# QuadADSR-v1.net
KiCad netlist of a schematic drawn in EAGLE
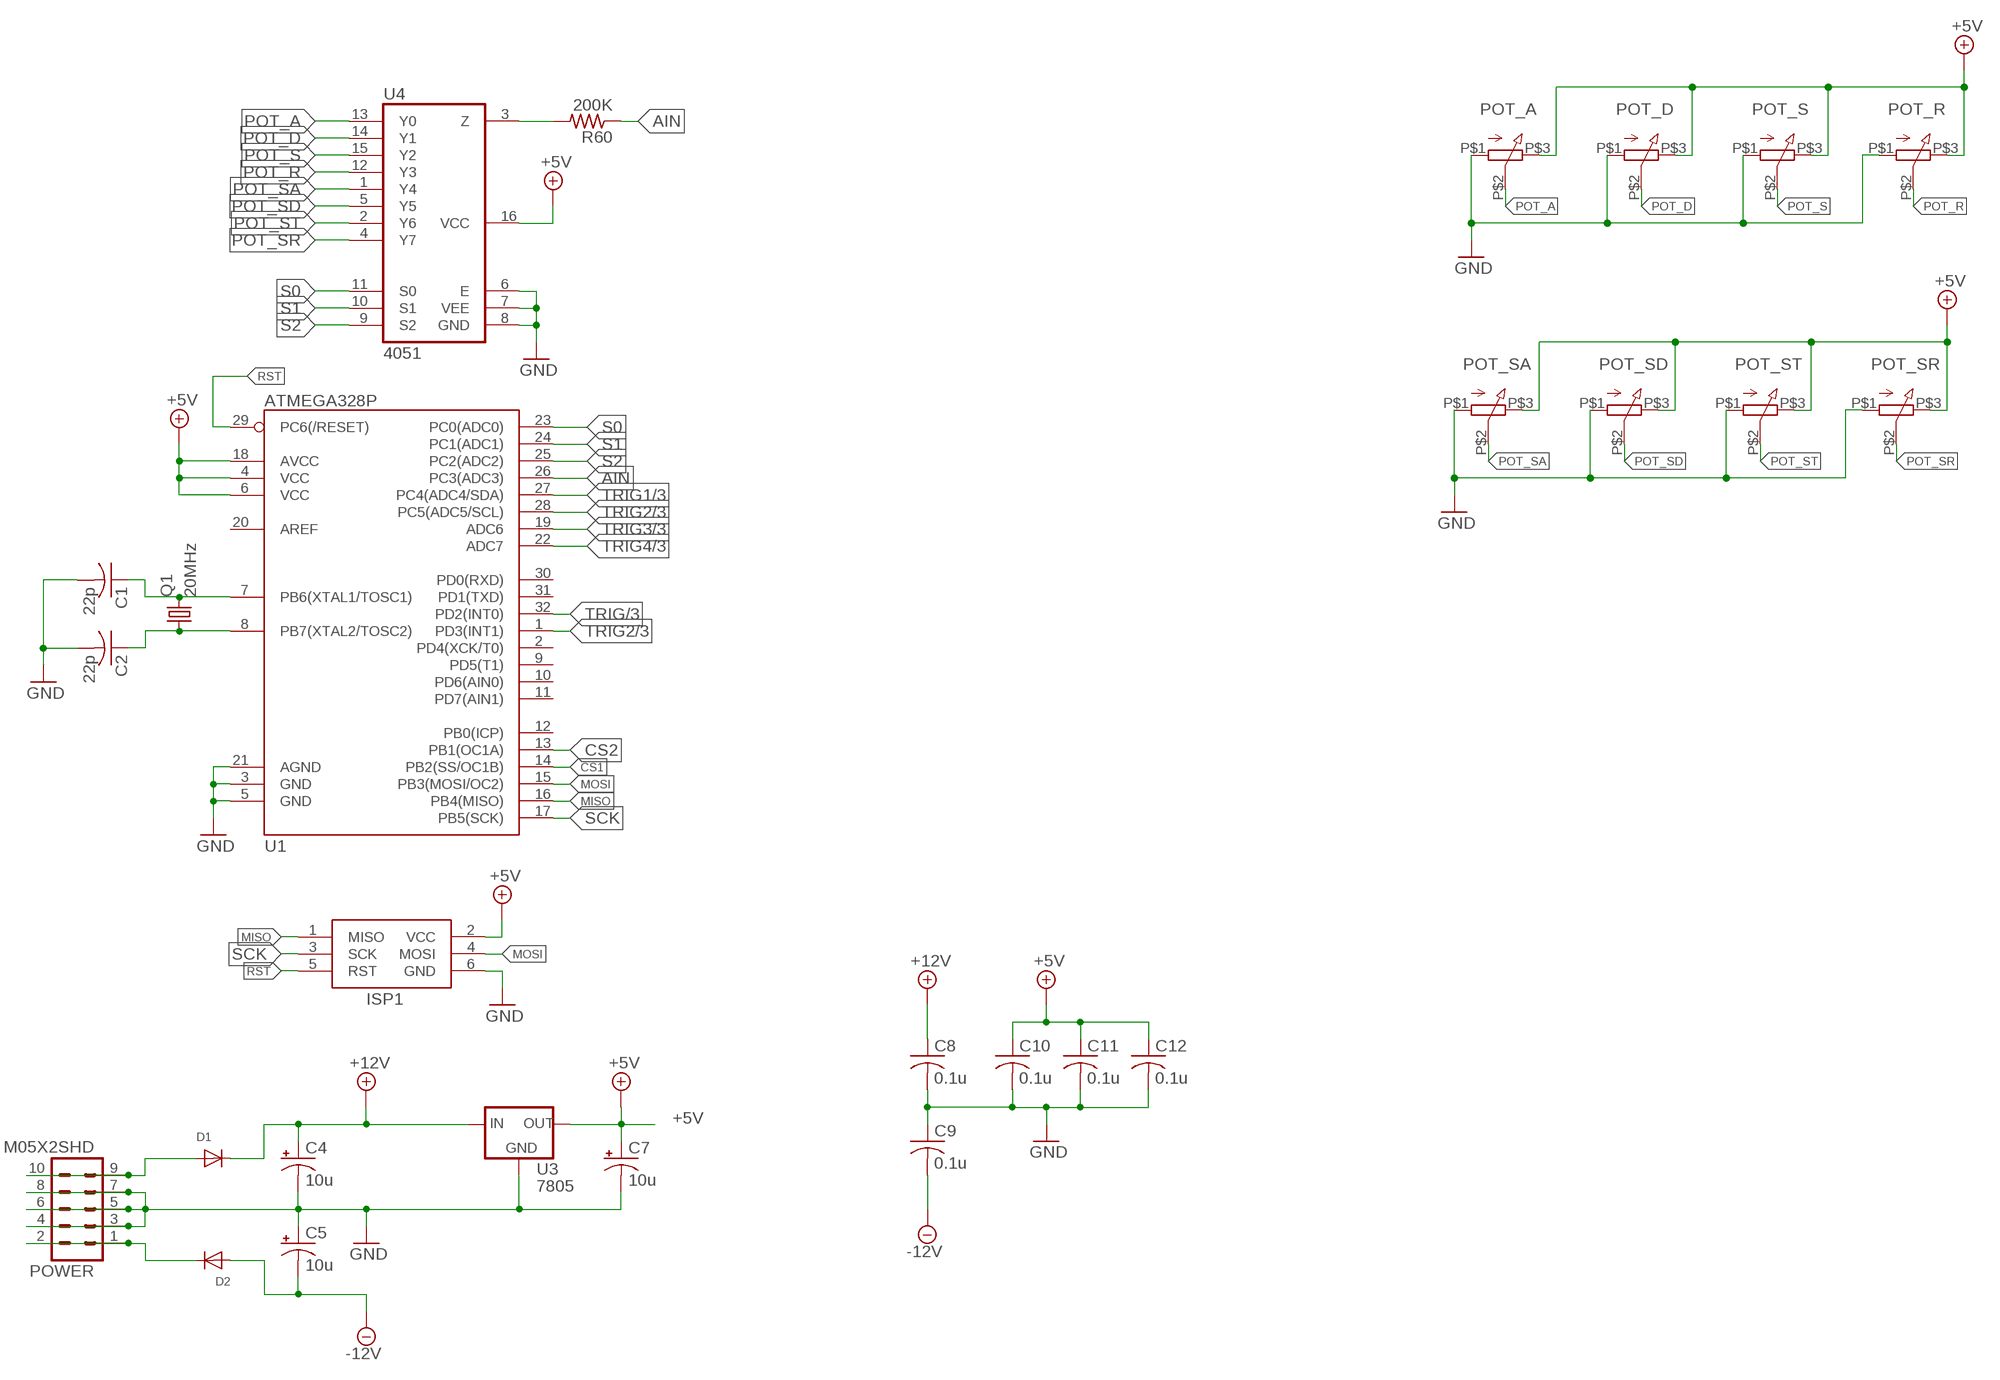
[diagram p0: schematic, sheet 1]
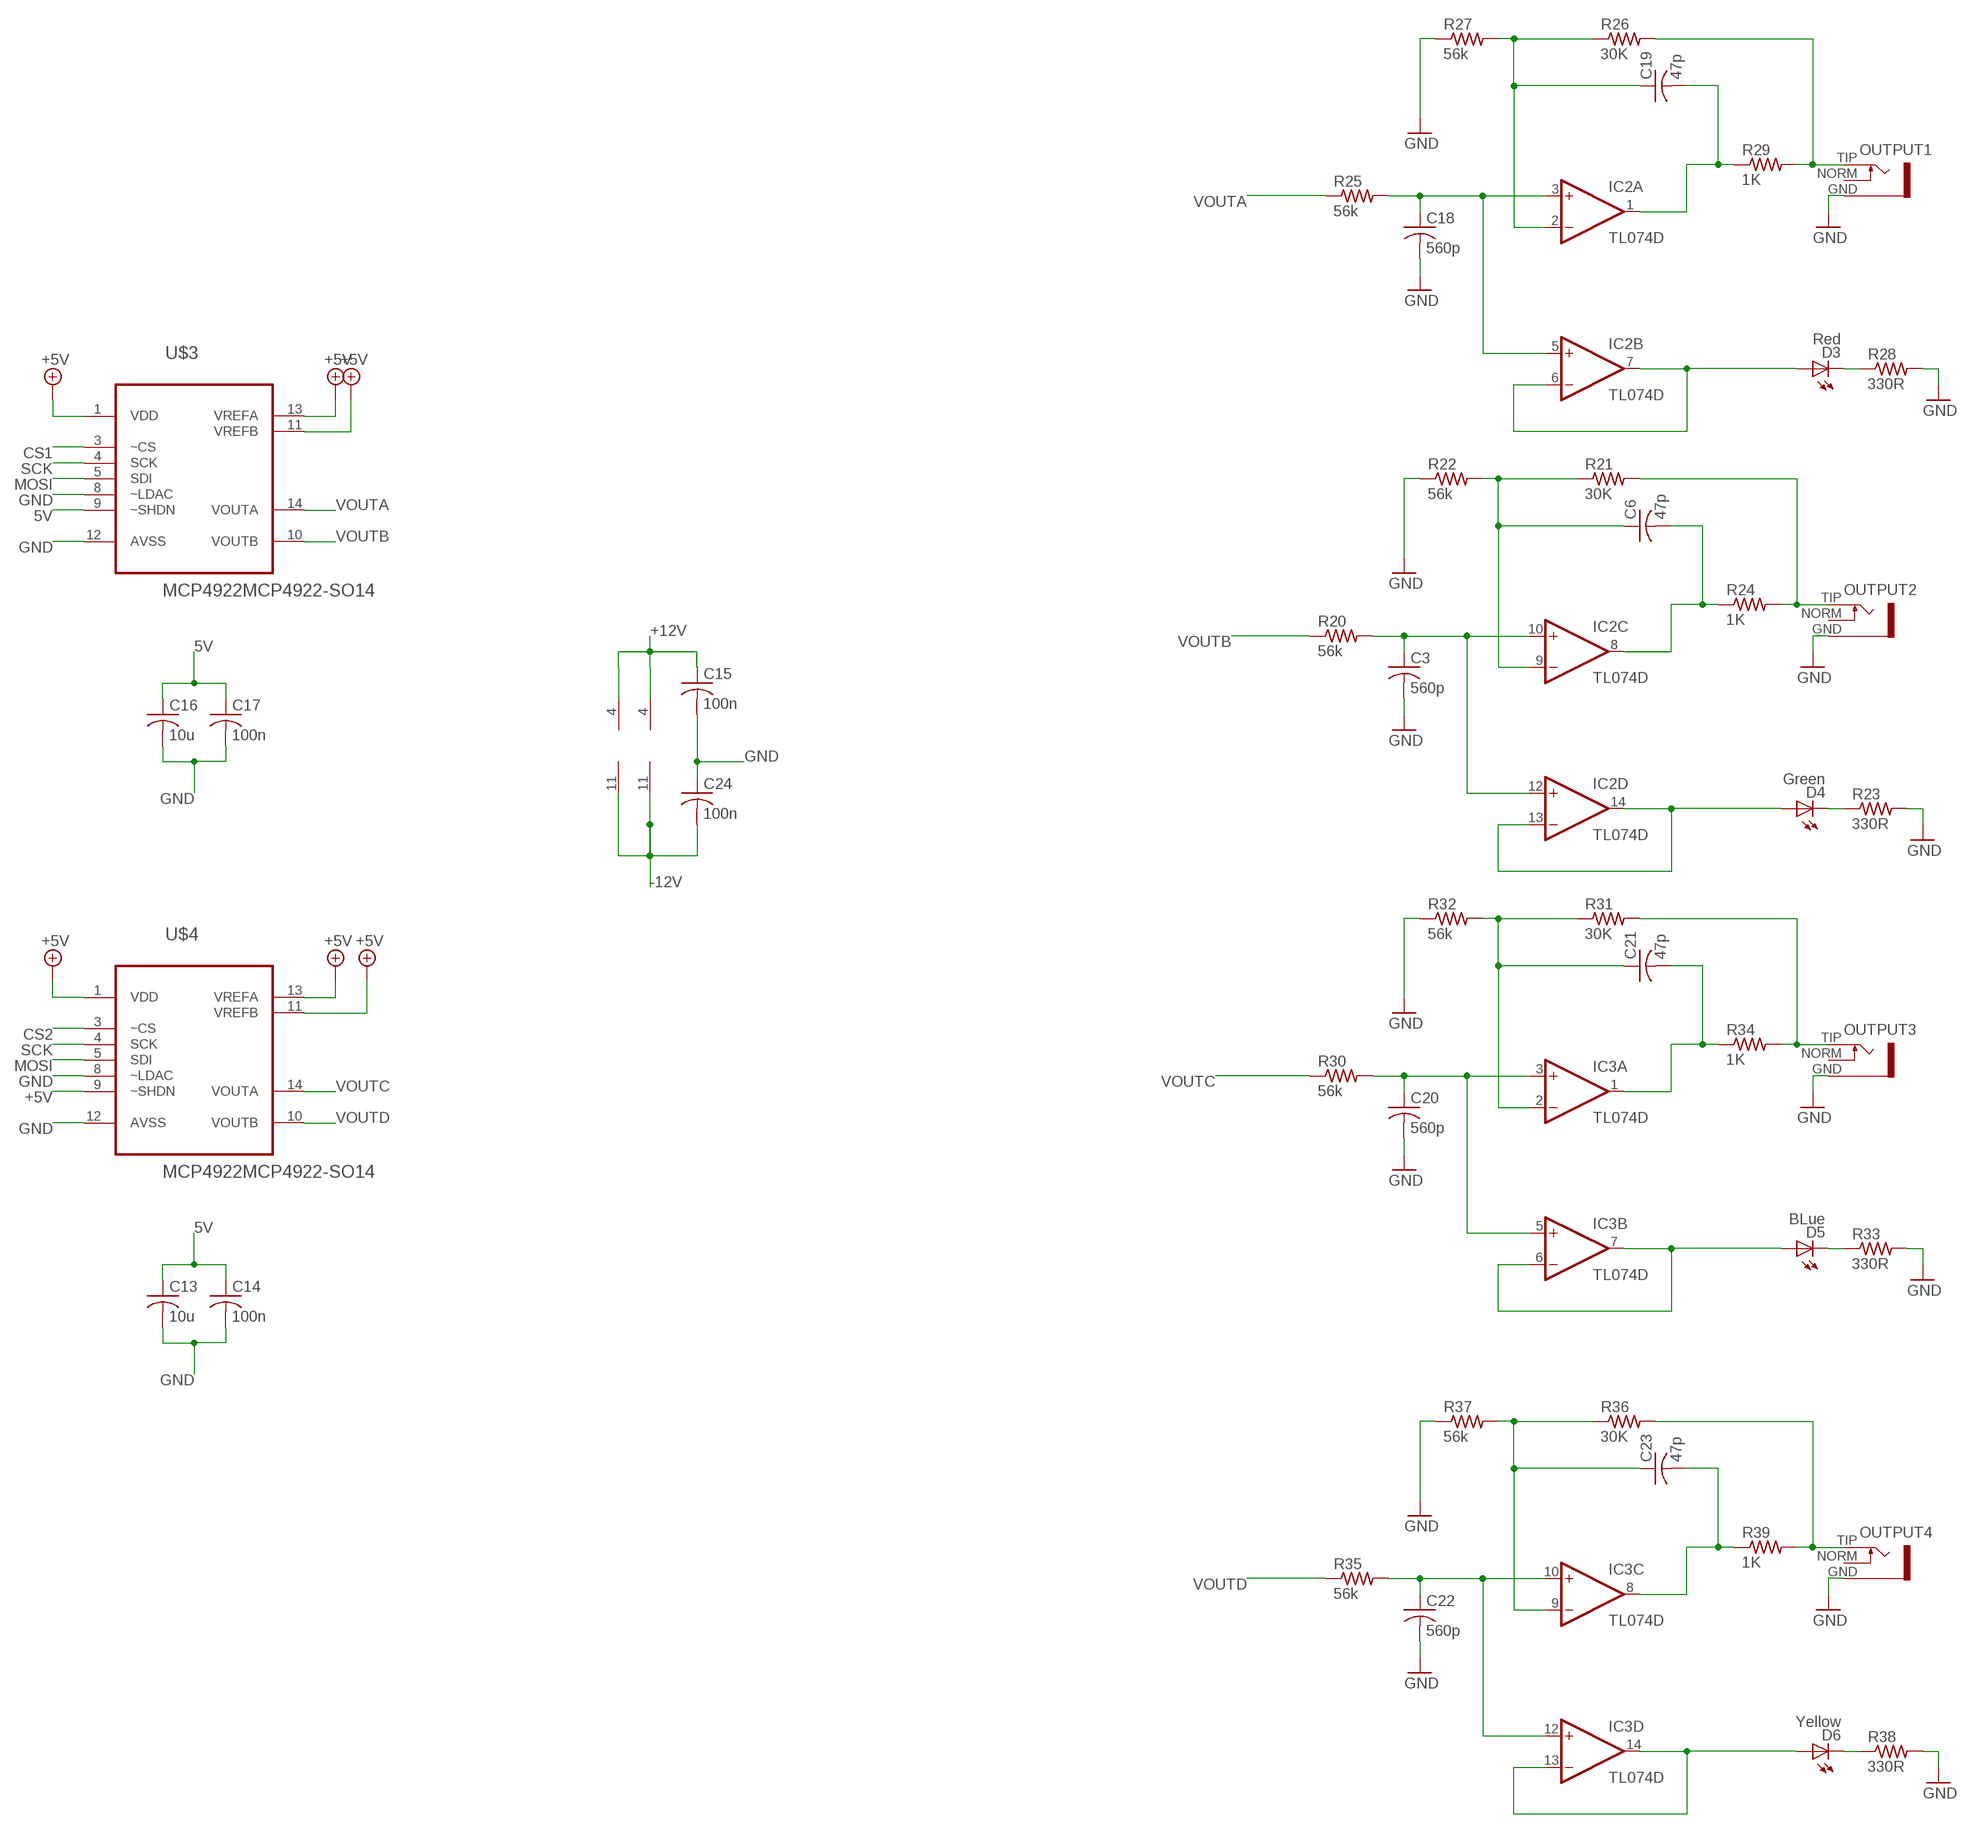
[diagram p1: schematic, sheet 2]
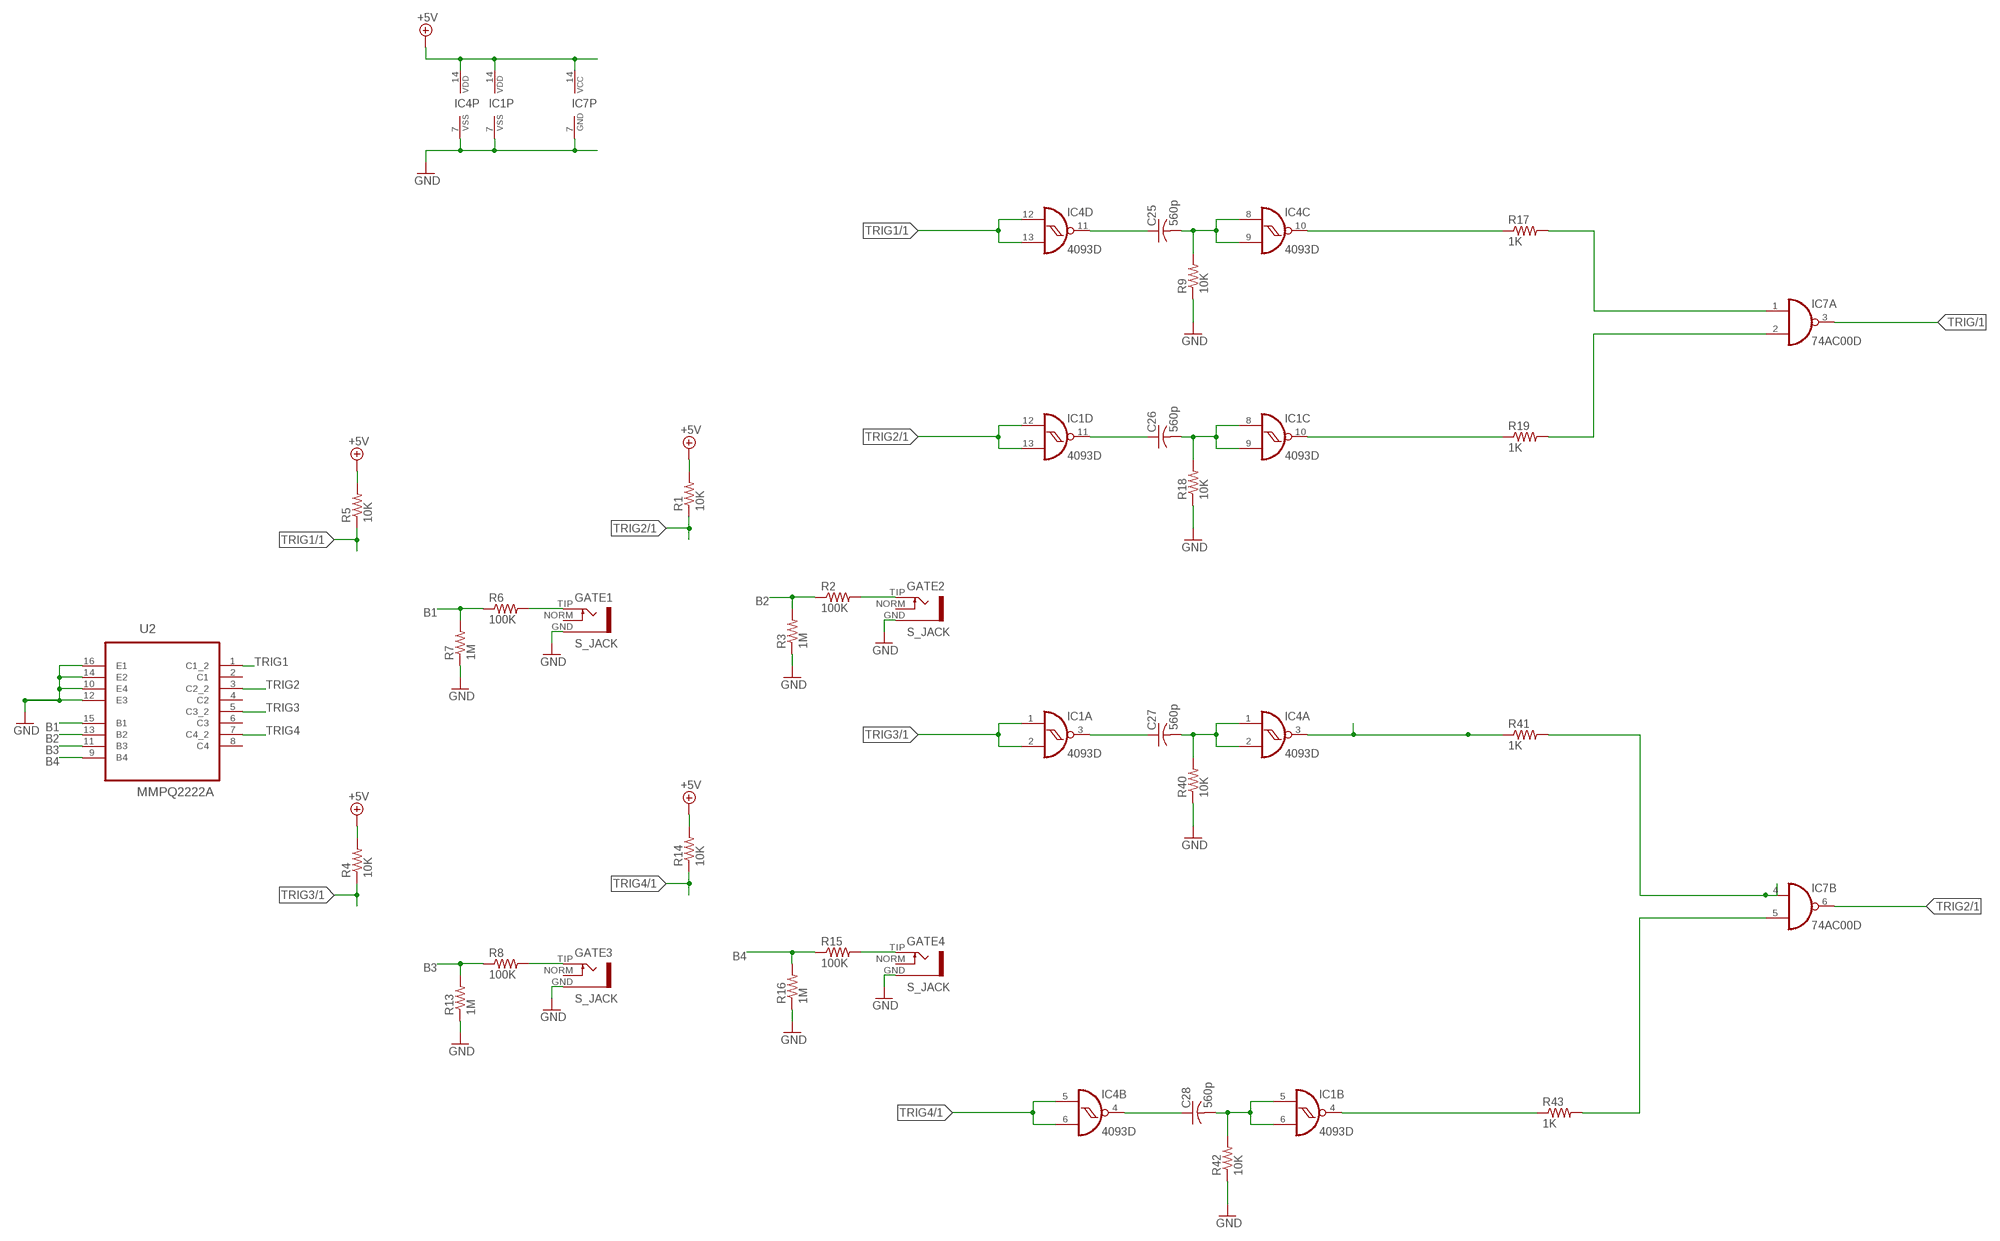
[diagram p2: schematic, sheet 3]

(export (version "E")
  (design (tool "Eeschema 10.0.6"))
  (components
    (comp (ref "C25")
      (value "560p")
      (footprint "eagle-import:C0805K")
      (libsource (lib "eagle-import") (part "C-USC0805K"))
    )
    (comp (ref "C26")
      (value "560p")
      (footprint "eagle-import:C0805K")
      (libsource (lib "eagle-import") (part "C-USC0805K"))
    )
    (comp (ref "C27")
      (value "560p")
      (footprint "eagle-import:C0805K")
      (libsource (lib "eagle-import") (part "C-USC0805K"))
    )
    (comp (ref "C28")
      (value "560p")
      (footprint "eagle-import:C0805K")
      (libsource (lib "eagle-import") (part "C-USC0805K"))
    )
    (comp (ref "GATE1")
      (value "S_JACK")
      (footprint "eagle-import:S_JACK")
      (libsource (lib "eagle-import") (part "S_JACK"))
    )
    (comp (ref "GATE2")
      (value "S_JACK")
      (footprint "eagle-import:S_JACK")
      (libsource (lib "eagle-import") (part "S_JACK"))
    )
    (comp (ref "GATE3")
      (value "S_JACK")
      (footprint "eagle-import:S_JACK")
      (libsource (lib "eagle-import") (part "S_JACK"))
    )
    (comp (ref "GATE4")
      (value "S_JACK")
      (footprint "eagle-import:S_JACK")
      (libsource (lib "eagle-import") (part "S_JACK"))
    )
    (comp (ref "IC1")
      (value "4093D")
      (footprint "eagle-import:SO14")
      (libsource (lib "eagle-import") (part "4093D"))
    )
    (comp (ref "IC4")
      (value "4093D")
      (footprint "eagle-import:SO14")
      (libsource (lib "eagle-import") (part "4093D"))
    )
    (comp (ref "IC7")
      (value "74AC00D")
      (footprint "eagle-import:SO14")
      (libsource (lib "eagle-import") (part "7400DAC"))
    )
    (comp (ref "R1")
      (value "10K")
      (footprint "eagle-import:R0805")
      (libsource (lib "eagle-import") (part "rcl_334_R-US_R0805"))
    )
    (comp (ref "R2")
      (value "100K")
      (footprint "eagle-import:R0805")
      (libsource (lib "eagle-import") (part "rcl_334_R-US_R0805"))
    )
    (comp (ref "R3")
      (value "1M")
      (footprint "eagle-import:R0805")
      (libsource (lib "eagle-import") (part "rcl_334_R-US_R0805"))
    )
    (comp (ref "R4")
      (value "10K")
      (footprint "eagle-import:R0805")
      (libsource (lib "eagle-import") (part "rcl_334_R-US_R0805"))
    )
    (comp (ref "R5")
      (value "10K")
      (footprint "eagle-import:R0805")
      (libsource (lib "eagle-import") (part "rcl_334_R-US_R0805"))
    )
    (comp (ref "R6")
      (value "100K")
      (footprint "eagle-import:R0805")
      (libsource (lib "eagle-import") (part "rcl_334_R-US_R0805"))
    )
    (comp (ref "R7")
      (value "1M")
      (footprint "eagle-import:R0805")
      (libsource (lib "eagle-import") (part "rcl_334_R-US_R0805"))
    )
    (comp (ref "R8")
      (value "100K")
      (footprint "eagle-import:R0805")
      (libsource (lib "eagle-import") (part "rcl_334_R-US_R0805"))
    )
    (comp (ref "R9")
      (value "10K")
      (footprint "eagle-import:R0805")
      (libsource (lib "eagle-import") (part "R-US_R0805"))
    )
    (comp (ref "R13")
      (value "1M")
      (footprint "eagle-import:R0805")
      (libsource (lib "eagle-import") (part "rcl_334_R-US_R0805"))
    )
    (comp (ref "R14")
      (value "10K")
      (footprint "eagle-import:R0805")
      (libsource (lib "eagle-import") (part "rcl_334_R-US_R0805"))
    )
    (comp (ref "R15")
      (value "100K")
      (footprint "eagle-import:R0805")
      (libsource (lib "eagle-import") (part "rcl_334_R-US_R0805"))
    )
    (comp (ref "R16")
      (value "1M")
      (footprint "eagle-import:R0805")
      (libsource (lib "eagle-import") (part "rcl_334_R-US_R0805"))
    )
    (comp (ref "R17")
      (value "1K")
      (footprint "eagle-import:R0805")
      (libsource (lib "eagle-import") (part "R-US_R0805"))
    )
    (comp (ref "R18")
      (value "10K")
      (footprint "eagle-import:R0805")
      (libsource (lib "eagle-import") (part "R-US_R0805"))
    )
    (comp (ref "R19")
      (value "1K")
      (footprint "eagle-import:R0805")
      (libsource (lib "eagle-import") (part "R-US_R0805"))
    )
    (comp (ref "R40")
      (value "10K")
      (footprint "eagle-import:R0805")
      (libsource (lib "eagle-import") (part "R-US_R0805"))
    )
    (comp (ref "R41")
      (value "1K")
      (footprint "eagle-import:R0805")
      (libsource (lib "eagle-import") (part "R-US_R0805"))
    )
    (comp (ref "R42")
      (value "10K")
      (footprint "eagle-import:R0805")
      (libsource (lib "eagle-import") (part "R-US_R0805"))
    )
    (comp (ref "R43")
      (value "1K")
      (footprint "eagle-import:R0805")
      (libsource (lib "eagle-import") (part "R-US_R0805"))
    )
    (comp (ref "U2")
      (value "MMPQ2222A")
      (footprint "eagle-import:SOIC127P600X175-16N")
      (libsource (lib "eagle-import") (part "MMPQ2222A"))
    )
    (comp (ref "C1")
      (value "22p")
      (footprint "eagle-import:C0805K")
      (libsource (lib "eagle-import") (part "rcl_334_C-USC0805K"))
    )
    (comp (ref "C2")
      (value "22p")
      (footprint "eagle-import:C0805K")
      (libsource (lib "eagle-import") (part "rcl_334_C-USC0805K"))
    )
    (comp (ref "C4")
      (value "10u")
      (footprint "eagle-import:153CLV-0505")
      (libsource (lib "eagle-import") (part "CPOL-US153CLV-0505"))
    )
    (comp (ref "C5")
      (value "10u")
      (footprint "eagle-import:153CLV-0505")
      (libsource (lib "eagle-import") (part "CPOL-US153CLV-0505"))
    )
    (comp (ref "C7")
      (value "10u")
      (footprint "eagle-import:153CLV-0505")
      (libsource (lib "eagle-import") (part "CPOL-US153CLV-0505"))
    )
    (comp (ref "C8")
      (value "0.1u")
      (footprint "eagle-import:C0805K")
      (libsource (lib "eagle-import") (part "rcl_334_C-USC0805K"))
    )
    (comp (ref "C9")
      (value "0.1u")
      (footprint "eagle-import:C0805K")
      (libsource (lib "eagle-import") (part "rcl_334_C-USC0805K"))
    )
    (comp (ref "C10")
      (value "0.1u")
      (footprint "eagle-import:C0805K")
      (libsource (lib "eagle-import") (part "rcl_334_C-USC0805K"))
    )
    (comp (ref "C11")
      (value "0.1u")
      (footprint "eagle-import:C0805K")
      (libsource (lib "eagle-import") (part "rcl_334_C-USC0805K"))
    )
    (comp (ref "C12")
      (value "0.1u")
      (footprint "eagle-import:C0805K")
      (libsource (lib "eagle-import") (part "rcl_334_C-USC0805K"))
    )
    (comp (ref "D1")
      (value "DIODESMA")
      (footprint "eagle-import:SMADIODE")
      (libsource (lib "eagle-import") (part "DIODESMA"))
    )
    (comp (ref "D2")
      (value "DIODESMA")
      (footprint "eagle-import:SMADIODE")
      (libsource (lib "eagle-import") (part "DIODESMA"))
    )
    (comp (ref "ISP1")
      (value "AVRISP-6")
      (footprint "eagle-import:AVRISP")
      (libsource (lib "eagle-import") (part "AVRISP-6"))
    )
    (comp (ref "POT_A")
      (value "Q-POT")
      (footprint "eagle-import:Q-POT")
      (libsource (lib "eagle-import") (part "Q-POT"))
    )
    (comp (ref "POT_D")
      (value "Q-POT")
      (footprint "eagle-import:Q-POT")
      (libsource (lib "eagle-import") (part "Q-POT"))
    )
    (comp (ref "POT_R")
      (value "Q-POT")
      (footprint "eagle-import:Q-POT")
      (libsource (lib "eagle-import") (part "Q-POT"))
    )
    (comp (ref "POT_S")
      (value "Q-POT")
      (footprint "eagle-import:Q-POT")
      (libsource (lib "eagle-import") (part "Q-POT"))
    )
    (comp (ref "POT_SA")
      (value "Q-POT")
      (footprint "eagle-import:Q-POT")
      (libsource (lib "eagle-import") (part "Q-POT"))
    )
    (comp (ref "POT_SD")
      (value "Q-POT")
      (footprint "eagle-import:Q-POT")
      (libsource (lib "eagle-import") (part "Q-POT"))
    )
    (comp (ref "POT_SR")
      (value "Q-POT")
      (footprint "eagle-import:Q-POT")
      (libsource (lib "eagle-import") (part "Q-POT"))
    )
    (comp (ref "POT_ST")
      (value "Q-POT")
      (footprint "eagle-import:Q-POT")
      (libsource (lib "eagle-import") (part "Q-POT"))
    )
    (comp (ref "POWER")
      (value "M05X2SHD")
      (footprint "eagle-import:2X5-SHROUDED")
      (libsource (lib "eagle-import") (part "M05X2SHD"))
    )
    (comp (ref "Q1")
      (value "20MHz")
      (footprint "eagle-import:HC49UP")
      (libsource (lib "eagle-import") (part "CRYSTALHC49UP"))
    )
    (comp (ref "R60")
      (value "200K")
      (footprint "eagle-import:R0805")
      (libsource (lib "eagle-import") (part "R-US_R0805"))
    )
    (comp (ref "U1")
      (value "ATMEGA328P")
      (footprint "eagle-import:TQFP32-08")
      (libsource (lib "eagle-import") (part "ATMEGA328_SMT"))
    )
    (comp (ref "U3")
      (value "7805")
      (footprint "eagle-import:V-REG")
      (libsource (lib "eagle-import") (part "V-REG"))
    )
    (comp (ref "U4")
      (value "4051")
      (footprint "eagle-import:N2222_ARRAY")
      (libsource (lib "eagle-import") (part "MUX!"))
    )
    (comp (ref "C3")
      (value "560p")
      (footprint "eagle-import:C0805K")
      (libsource (lib "eagle-import") (part "C-USC0805K"))
    )
    (comp (ref "C6")
      (value "47p")
      (footprint "eagle-import:C0805K")
      (libsource (lib "eagle-import") (part "C-USC0805K"))
    )
    (comp (ref "C13")
      (value "10u")
      (footprint "eagle-import:C0805K")
      (libsource (lib "eagle-import") (part "rcl_334_C-USC0805K"))
    )
    (comp (ref "C14")
      (value "100n")
      (footprint "eagle-import:C0805K")
      (libsource (lib "eagle-import") (part "rcl_334_C-USC0805K"))
    )
    (comp (ref "C15")
      (value "100n")
      (footprint "eagle-import:C0805K")
      (libsource (lib "eagle-import") (part "rcl_334_C-USC0805K"))
    )
    (comp (ref "C16")
      (value "10u")
      (footprint "eagle-import:C0805K")
      (libsource (lib "eagle-import") (part "rcl_334_C-USC0805K"))
    )
    (comp (ref "C17")
      (value "100n")
      (footprint "eagle-import:C0805K")
      (libsource (lib "eagle-import") (part "rcl_334_C-USC0805K"))
    )
    (comp (ref "C18")
      (value "560p")
      (footprint "eagle-import:C0805K")
      (libsource (lib "eagle-import") (part "C-USC0805K"))
    )
    (comp (ref "C19")
      (value "47p")
      (footprint "eagle-import:C0805K")
      (libsource (lib "eagle-import") (part "C-USC0805K"))
    )
    (comp (ref "C20")
      (value "560p")
      (footprint "eagle-import:C0805K")
      (libsource (lib "eagle-import") (part "C-USC0805K"))
    )
    (comp (ref "C21")
      (value "47p")
      (footprint "eagle-import:C0805K")
      (libsource (lib "eagle-import") (part "C-USC0805K"))
    )
    (comp (ref "C22")
      (value "560p")
      (footprint "eagle-import:C0805K")
      (libsource (lib "eagle-import") (part "C-USC0805K"))
    )
    (comp (ref "C23")
      (value "47p")
      (footprint "eagle-import:C0805K")
      (libsource (lib "eagle-import") (part "C-USC0805K"))
    )
    (comp (ref "C24")
      (value "100n")
      (footprint "eagle-import:C0805K")
      (libsource (lib "eagle-import") (part "rcl_334_C-USC0805K"))
    )
    (comp (ref "D3")
      (value "Red")
      (footprint "eagle-import:LED5MM")
      (libsource (lib "eagle-import") (part "LED5MM"))
    )
    (comp (ref "D4")
      (value "Green")
      (footprint "eagle-import:LED5MM")
      (libsource (lib "eagle-import") (part "LED5MM"))
    )
    (comp (ref "D5")
      (value "BLue")
      (footprint "eagle-import:LED5MM")
      (libsource (lib "eagle-import") (part "LED5MM"))
    )
    (comp (ref "D6")
      (value "Yellow")
      (footprint "eagle-import:LED5MM")
      (libsource (lib "eagle-import") (part "LED5MM"))
    )
    (comp (ref "IC2")
      (value "TL074D")
      (footprint "eagle-import:SO14")
      (libsource (lib "eagle-import") (part "TL074D"))
    )
    (comp (ref "IC3")
      (value "TL074D")
      (footprint "eagle-import:SO14")
      (libsource (lib "eagle-import") (part "TL074D"))
    )
    (comp (ref "OUTPUT1")
      (value "S_JACK")
      (footprint "eagle-import:S_JACK")
      (libsource (lib "eagle-import") (part "S_JACK"))
    )
    (comp (ref "OUTPUT2")
      (value "S_JACK")
      (footprint "eagle-import:S_JACK")
      (libsource (lib "eagle-import") (part "S_JACK"))
    )
    (comp (ref "OUTPUT3")
      (value "S_JACK")
      (footprint "eagle-import:S_JACK")
      (libsource (lib "eagle-import") (part "S_JACK"))
    )
    (comp (ref "OUTPUT4")
      (value "S_JACK")
      (footprint "eagle-import:S_JACK")
      (libsource (lib "eagle-import") (part "S_JACK"))
    )
    (comp (ref "R20")
      (value "56k")
      (footprint "eagle-import:R0805")
      (libsource (lib "eagle-import") (part "R-US_R0805"))
    )
    (comp (ref "R21")
      (value "30K")
      (footprint "eagle-import:R0805")
      (libsource (lib "eagle-import") (part "R-US_R0805"))
    )
    (comp (ref "R22")
      (value "56k")
      (footprint "eagle-import:R0805")
      (libsource (lib "eagle-import") (part "R-US_R0805"))
    )
    (comp (ref "R23")
      (value "330R")
      (footprint "eagle-import:R0805")
      (libsource (lib "eagle-import") (part "R-US_R0805"))
    )
    (comp (ref "R24")
      (value "1K")
      (footprint "eagle-import:R0805")
      (libsource (lib "eagle-import") (part "R-US_R0805"))
    )
    (comp (ref "R25")
      (value "56k")
      (footprint "eagle-import:R0805")
      (libsource (lib "eagle-import") (part "R-US_R0805"))
    )
    (comp (ref "R26")
      (value "30K")
      (footprint "eagle-import:R0805")
      (libsource (lib "eagle-import") (part "R-US_R0805"))
    )
    (comp (ref "R27")
      (value "56k")
      (footprint "eagle-import:R0805")
      (libsource (lib "eagle-import") (part "R-US_R0805"))
    )
    (comp (ref "R28")
      (value "330R")
      (footprint "eagle-import:R0805")
      (libsource (lib "eagle-import") (part "R-US_R0805"))
    )
    (comp (ref "R29")
      (value "1K")
      (footprint "eagle-import:R0805")
      (libsource (lib "eagle-import") (part "R-US_R0805"))
    )
    (comp (ref "R30")
      (value "56k")
      (footprint "eagle-import:R0805")
      (libsource (lib "eagle-import") (part "R-US_R0805"))
    )
    (comp (ref "R31")
      (value "30K")
      (footprint "eagle-import:R0805")
      (libsource (lib "eagle-import") (part "R-US_R0805"))
    )
    (comp (ref "R32")
      (value "56k")
      (footprint "eagle-import:R0805")
      (libsource (lib "eagle-import") (part "R-US_R0805"))
    )
    (comp (ref "R33")
      (value "330R")
      (footprint "eagle-import:R0805")
      (libsource (lib "eagle-import") (part "R-US_R0805"))
    )
    (comp (ref "R34")
      (value "1K")
      (footprint "eagle-import:R0805")
      (libsource (lib "eagle-import") (part "R-US_R0805"))
    )
    (comp (ref "R35")
      (value "56k")
      (footprint "eagle-import:R0805")
      (libsource (lib "eagle-import") (part "R-US_R0805"))
    )
    (comp (ref "R36")
      (value "30K")
      (footprint "eagle-import:R0805")
      (libsource (lib "eagle-import") (part "R-US_R0805"))
    )
    (comp (ref "R37")
      (value "56k")
      (footprint "eagle-import:R0805")
      (libsource (lib "eagle-import") (part "R-US_R0805"))
    )
    (comp (ref "R38")
      (value "330R")
      (footprint "eagle-import:R0805")
      (libsource (lib "eagle-import") (part "R-US_R0805"))
    )
    (comp (ref "R39")
      (value "1K")
      (footprint "eagle-import:R0805")
      (libsource (lib "eagle-import") (part "R-US_R0805"))
    )
    (comp (ref "U$3")
      (value "MCP4922MCP4922-SO14")
      (footprint "eagle-import:SO14")
      (libsource (lib "eagle-import") (part "MCP4922MCP4922-SO14"))
    )
    (comp (ref "U$4")
      (value "MCP4922MCP4922-SO14")
      (footprint "eagle-import:SO14")
      (libsource (lib "eagle-import") (part "MCP4922MCP4922-SO14"))
    )
  )
  (nets
    (net (code "1") (name "+5V") (class "Default")
      (node (ref "C10") (pin "1") (pinfunction "1_1") (pintype "passive"))
      (node (ref "C11") (pin "1") (pinfunction "1_1") (pintype "passive"))
      (node (ref "C12") (pin "1") (pinfunction "1_1") (pintype "passive"))
      (node (ref "C7") (pin "+") (pinfunction "+_+") (pintype "passive"))
      (node (ref "IC1") (pin "14") (pinfunction "VDD_14") (pintype "power_in"))
      (node (ref "IC4") (pin "14") (pinfunction "VDD_14") (pintype "power_in"))
      (node (ref "IC7") (pin "14") (pinfunction "VCC_14") (pintype "power_in"))
      (node (ref "ISP1") (pin "2") (pinfunction "VCC_2") (pintype "power_in"))
      (node (ref "POT_A") (pin "P$3") (pinfunction "3_P$3") (pintype "passive"))
      (node (ref "POT_D") (pin "P$3") (pinfunction "3_P$3") (pintype "passive"))
      (node (ref "POT_R") (pin "P$3") (pinfunction "3_P$3") (pintype "passive"))
      (node (ref "POT_S") (pin "P$3") (pinfunction "3_P$3") (pintype "passive"))
      (node (ref "POT_SA") (pin "P$3") (pinfunction "3_P$3") (pintype "passive"))
      (node (ref "POT_SD") (pin "P$3") (pinfunction "3_P$3") (pintype "passive"))
      (node (ref "POT_SR") (pin "P$3") (pinfunction "3_P$3") (pintype "passive"))
      (node (ref "POT_ST") (pin "P$3") (pinfunction "3_P$3") (pintype "passive"))
      (node (ref "R1") (pin "2") (pinfunction "2_2") (pintype "passive"))
      (node (ref "R14") (pin "2") (pinfunction "2_2") (pintype "passive"))
      (node (ref "R4") (pin "2") (pinfunction "2_2") (pintype "passive"))
      (node (ref "R5") (pin "2") (pinfunction "2_2") (pintype "passive"))
      (node (ref "U$3") (pin "1") (pinfunction "VDD_1") (pintype "power_in"))
      (node (ref "U$3") (pin "11") (pinfunction "VREFB_11") (pintype "bidirectional"))
      (node (ref "U$3") (pin "13") (pinfunction "VREFA_13") (pintype "input"))
      (node (ref "U$4") (pin "1") (pinfunction "VDD_1") (pintype "power_in"))
      (node (ref "U$4") (pin "11") (pinfunction "VREFB_11") (pintype "bidirectional"))
      (node (ref "U$4") (pin "13") (pinfunction "VREFA_13") (pintype "input"))
      (node (ref "U$4") (pin "9") (pinfunction "~{SHDN}_9") (pintype "bidirectional"))
      (node (ref "U1") (pin "18") (pinfunction "AVCC_18") (pintype "bidirectional"))
      (node (ref "U1") (pin "4") (pinfunction "VCC_4") (pintype "bidirectional"))
      (node (ref "U1") (pin "6") (pinfunction "VCC_6") (pintype "bidirectional"))
      (node (ref "U3") (pin "3") (pinfunction "OUT_3") (pintype "passive"))
      (node (ref "U4") (pin "16") (pinfunction "VCC_16") (pintype "input"))
    )
    (net (code "2") (name "+12V") (class "Default")
      (node (ref "C15") (pin "1") (pinfunction "1_1") (pintype "passive"))
      (node (ref "C4") (pin "+") (pinfunction "+_+") (pintype "passive"))
      (node (ref "C8") (pin "1") (pinfunction "1_1") (pintype "passive"))
      (node (ref "D1") (pin "C") (pinfunction "C_C") (pintype "passive"))
      (node (ref "IC2") (pin "4") (pinfunction "V+_4") (pintype "power_in"))
      (node (ref "IC3") (pin "4") (pinfunction "V+_4") (pintype "power_in"))
      (node (ref "U3") (pin "1") (pinfunction "IN_1") (pintype "input"))
    )
    (net (code "3") (name "-12V") (class "Default")
      (node (ref "C24") (pin "2") (pinfunction "2_2") (pintype "passive"))
      (node (ref "C5") (pin "-") (pinfunction "-_-") (pintype "passive"))
      (node (ref "C9") (pin "2") (pinfunction "2_2") (pintype "passive"))
      (node (ref "D2") (pin "A") (pinfunction "A_A") (pintype "passive"))
      (node (ref "IC2") (pin "11") (pinfunction "V-_11") (pintype "power_in"))
      (node (ref "IC3") (pin "11") (pinfunction "V-_11") (pintype "power_in"))
    )
    (net (code "4") (name "5V") (class "Default")
      (node (ref "C13") (pin "1") (pinfunction "1_1") (pintype "passive"))
      (node (ref "C14") (pin "1") (pinfunction "1_1") (pintype "passive"))
      (node (ref "C16") (pin "1") (pinfunction "1_1") (pintype "passive"))
      (node (ref "C17") (pin "1") (pinfunction "1_1") (pintype "passive"))
      (node (ref "U$3") (pin "9") (pinfunction "~{SHDN}_9") (pintype "bidirectional"))
    )
    (net (code "5") (name "AIN") (class "Default")
      (node (ref "R60") (pin "1") (pinfunction "1_1") (pintype "passive"))
      (node (ref "U1") (pin "26") (pinfunction "PC3(ADC3)_26") (pintype "bidirectional"))
    )
    (net (code "6") (name "B1") (class "Default")
      (node (ref "R6") (pin "1") (pinfunction "1_1") (pintype "passive"))
      (node (ref "R7") (pin "2") (pinfunction "2_2") (pintype "passive"))
      (node (ref "U2") (pin "15") (pinfunction "B1_15") (pintype "passive"))
    )
    (net (code "7") (name "B2") (class "Default")
      (node (ref "R2") (pin "1") (pinfunction "1_1") (pintype "passive"))
      (node (ref "R3") (pin "2") (pinfunction "2_2") (pintype "passive"))
      (node (ref "U2") (pin "13") (pinfunction "B2_13") (pintype "passive"))
    )
    (net (code "8") (name "B3") (class "Default")
      (node (ref "R13") (pin "2") (pinfunction "2_2") (pintype "passive"))
      (node (ref "R8") (pin "1") (pinfunction "1_1") (pintype "passive"))
      (node (ref "U2") (pin "11") (pinfunction "B3_11") (pintype "passive"))
    )
    (net (code "9") (name "B4") (class "Default")
      (node (ref "R15") (pin "1") (pinfunction "1_1") (pintype "passive"))
      (node (ref "R16") (pin "2") (pinfunction "2_2") (pintype "passive"))
      (node (ref "U2") (pin "9") (pinfunction "B4_9") (pintype "passive"))
    )
    (net (code "10") (name "CS1") (class "Default")
      (node (ref "U$3") (pin "3") (pinfunction "~{CS}_3") (pintype "input"))
      (node (ref "U1") (pin "14") (pinfunction "PB2(SS/OC1B)_14") (pintype "bidirectional"))
    )
    (net (code "11") (name "CS2") (class "Default")
      (node (ref "U$4") (pin "3") (pinfunction "~{CS}_3") (pintype "input"))
      (node (ref "U1") (pin "13") (pinfunction "PB1(OC1A)_13") (pintype "bidirectional"))
    )
    (net (code "12") (name "GND") (class "Default")
      (node (ref "C1") (pin "2") (pinfunction "2_2") (pintype "passive"))
      (node (ref "C10") (pin "2") (pinfunction "2_2") (pintype "passive"))
      (node (ref "C11") (pin "2") (pinfunction "2_2") (pintype "passive"))
      (node (ref "C12") (pin "2") (pinfunction "2_2") (pintype "passive"))
      (node (ref "C13") (pin "2") (pinfunction "2_2") (pintype "passive"))
      (node (ref "C14") (pin "2") (pinfunction "2_2") (pintype "passive"))
      (node (ref "C15") (pin "2") (pinfunction "2_2") (pintype "passive"))
      (node (ref "C16") (pin "2") (pinfunction "2_2") (pintype "passive"))
      (node (ref "C17") (pin "2") (pinfunction "2_2") (pintype "passive"))
      (node (ref "C18") (pin "2") (pinfunction "2_2") (pintype "passive"))
      (node (ref "C2") (pin "2") (pinfunction "2_2") (pintype "passive"))
      (node (ref "C20") (pin "2") (pinfunction "2_2") (pintype "passive"))
      (node (ref "C22") (pin "2") (pinfunction "2_2") (pintype "passive"))
      (node (ref "C24") (pin "1") (pinfunction "1_1") (pintype "passive"))
      (node (ref "C3") (pin "2") (pinfunction "2_2") (pintype "passive"))
      (node (ref "C4") (pin "-") (pinfunction "-_-") (pintype "passive"))
      (node (ref "C5") (pin "+") (pinfunction "+_+") (pintype "passive"))
      (node (ref "C7") (pin "-") (pinfunction "-_-") (pintype "passive"))
      (node (ref "C8") (pin "2") (pinfunction "2_2") (pintype "passive"))
      (node (ref "C9") (pin "1") (pinfunction "1_1") (pintype "passive"))
      (node (ref "GATE1") (pin "GND") (pinfunction "GND_GND") (pintype "passive"))
      (node (ref "GATE2") (pin "GND") (pinfunction "GND_GND") (pintype "passive"))
      (node (ref "GATE3") (pin "GND") (pinfunction "GND_GND") (pintype "passive"))
      (node (ref "GATE4") (pin "GND") (pinfunction "GND_GND") (pintype "passive"))
      (node (ref "IC1") (pin "7") (pinfunction "VSS_7") (pintype "power_in"))
      (node (ref "IC4") (pin "7") (pinfunction "VSS_7") (pintype "power_in"))
      (node (ref "IC7") (pin "7") (pinfunction "GND_7") (pintype "power_in"))
      (node (ref "ISP1") (pin "6") (pinfunction "GND_6") (pintype "power_in"))
      (node (ref "OUTPUT1") (pin "GND") (pinfunction "GND_GND") (pintype "passive"))
      (node (ref "OUTPUT2") (pin "GND") (pinfunction "GND_GND") (pintype "passive"))
      (node (ref "OUTPUT3") (pin "GND") (pinfunction "GND_GND") (pintype "passive"))
      (node (ref "OUTPUT4") (pin "GND") (pinfunction "GND_GND") (pintype "passive"))
      (node (ref "POT_A") (pin "P$1") (pinfunction "1_P$1") (pintype "passive"))
      (node (ref "POT_D") (pin "P$1") (pinfunction "1_P$1") (pintype "passive"))
      (node (ref "POT_R") (pin "P$1") (pinfunction "1_P$1") (pintype "passive"))
      (node (ref "POT_S") (pin "P$1") (pinfunction "1_P$1") (pintype "passive"))
      (node (ref "POT_SA") (pin "P$1") (pinfunction "1_P$1") (pintype "passive"))
      (node (ref "POT_SD") (pin "P$1") (pinfunction "1_P$1") (pintype "passive"))
      (node (ref "POT_SR") (pin "P$1") (pinfunction "1_P$1") (pintype "passive"))
      (node (ref "POT_ST") (pin "P$1") (pinfunction "1_P$1") (pintype "passive"))
      (node (ref "POWER") (pin "3") (pinfunction "3_3") (pintype "passive"))
      (node (ref "POWER") (pin "4") (pinfunction "4_4") (pintype "passive"))
      (node (ref "POWER") (pin "5") (pinfunction "5_5") (pintype "passive"))
      (node (ref "POWER") (pin "6") (pinfunction "6_6") (pintype "passive"))
      (node (ref "POWER") (pin "7") (pinfunction "7_7") (pintype "passive"))
      (node (ref "POWER") (pin "8") (pinfunction "8_8") (pintype "passive"))
      (node (ref "R13") (pin "1") (pinfunction "1_1") (pintype "passive"))
      (node (ref "R16") (pin "1") (pinfunction "1_1") (pintype "passive"))
      (node (ref "R18") (pin "1") (pinfunction "1_1") (pintype "passive"))
      (node (ref "R22") (pin "1") (pinfunction "1_1") (pintype "passive"))
      (node (ref "R23") (pin "2") (pinfunction "2_2") (pintype "passive"))
      (node (ref "R27") (pin "1") (pinfunction "1_1") (pintype "passive"))
      (node (ref "R28") (pin "2") (pinfunction "2_2") (pintype "passive"))
      (node (ref "R3") (pin "1") (pinfunction "1_1") (pintype "passive"))
      (node (ref "R32") (pin "1") (pinfunction "1_1") (pintype "passive"))
      (node (ref "R33") (pin "2") (pinfunction "2_2") (pintype "passive"))
      (node (ref "R37") (pin "1") (pinfunction "1_1") (pintype "passive"))
      (node (ref "R38") (pin "2") (pinfunction "2_2") (pintype "passive"))
      (node (ref "R40") (pin "1") (pinfunction "1_1") (pintype "passive"))
      (node (ref "R42") (pin "1") (pinfunction "1_1") (pintype "passive"))
      (node (ref "R7") (pin "1") (pinfunction "1_1") (pintype "passive"))
      (node (ref "R9") (pin "1") (pinfunction "1_1") (pintype "passive"))
      (node (ref "U$3") (pin "12") (pinfunction "AVSS_12") (pintype "passive"))
      (node (ref "U$3") (pin "8") (pinfunction "~{LDAC}_8") (pintype "input"))
      (node (ref "U$4") (pin "12") (pinfunction "AVSS_12") (pintype "passive"))
      (node (ref "U$4") (pin "8") (pinfunction "~{LDAC}_8") (pintype "input"))
      (node (ref "U1") (pin "21") (pinfunction "AGND_21") (pintype "bidirectional"))
      (node (ref "U1") (pin "3") (pinfunction "GND_3") (pintype "bidirectional"))
      (node (ref "U1") (pin "5") (pinfunction "GND_5") (pintype "bidirectional"))
      (node (ref "U2") (pin "10") (pinfunction "E4_10") (pintype "passive"))
      (node (ref "U2") (pin "12") (pinfunction "E3_12") (pintype "passive"))
      (node (ref "U2") (pin "14") (pinfunction "E2_14") (pintype "passive"))
      (node (ref "U2") (pin "16") (pinfunction "E1_16") (pintype "passive"))
      (node (ref "U3") (pin "4") (pinfunction "GND_4") (pintype "input"))
      (node (ref "U4") (pin "6") (pinfunction "E_6") (pintype "bidirectional"))
      (node (ref "U4") (pin "7") (pinfunction "VEE_7") (pintype "bidirectional"))
      (node (ref "U4") (pin "8") (pinfunction "GND_8") (pintype "bidirectional"))
    )
    (net (code "13") (name "MISO") (class "Default")
      (node (ref "ISP1") (pin "1") (pinfunction "MISO_1") (pintype "input"))
      (node (ref "U1") (pin "16") (pinfunction "PB4(MISO)_16") (pintype "bidirectional"))
    )
    (net (code "14") (name "MOSI") (class "Default")
      (node (ref "ISP1") (pin "4") (pinfunction "MOSI_4") (pintype "output"))
      (node (ref "U$3") (pin "5") (pinfunction "SDI_5") (pintype "input"))
      (node (ref "U$4") (pin "5") (pinfunction "SDI_5") (pintype "input"))
      (node (ref "U1") (pin "15") (pinfunction "PB3(MOSI/OC2)_15") (pintype "bidirectional"))
    )
    (net (code "15") (name "Net-(D1-PadA)") (class "Default")
      (node (ref "D1") (pin "A") (pinfunction "A_A") (pintype "passive"))
      (node (ref "POWER") (pin "10") (pinfunction "10_10") (pintype "passive"))
      (node (ref "POWER") (pin "9") (pinfunction "9_9") (pintype "passive"))
    )
    (net (code "16") (name "Net-(D2-PadC)") (class "Default")
      (node (ref "D2") (pin "C") (pinfunction "C_C") (pintype "passive"))
      (node (ref "POWER") (pin "1") (pinfunction "1_1") (pintype "passive"))
      (node (ref "POWER") (pin "2") (pinfunction "2_2") (pintype "passive"))
    )
    (net (code "17") (name "Net-(D3-C)") (class "Default")
      (node (ref "D3") (pin "K") (pinfunction "C_K") (pintype "passive"))
      (node (ref "R28") (pin "1") (pinfunction "1_1") (pintype "passive"))
    )
    (net (code "18") (name "Net-(D4-C)") (class "Default")
      (node (ref "D4") (pin "K") (pinfunction "C_K") (pintype "passive"))
      (node (ref "R23") (pin "1") (pinfunction "1_1") (pintype "passive"))
    )
    (net (code "19") (name "Net-(D5-C)") (class "Default")
      (node (ref "D5") (pin "K") (pinfunction "C_K") (pintype "passive"))
      (node (ref "R33") (pin "1") (pinfunction "1_1") (pintype "passive"))
    )
    (net (code "20") (name "Net-(D6-C)") (class "Default")
      (node (ref "D6") (pin "K") (pinfunction "C_K") (pintype "passive"))
      (node (ref "R38") (pin "1") (pinfunction "1_1") (pintype "passive"))
    )
    (net (code "21") (name "Net-(GATE1-PadTIP)") (class "Default")
      (node (ref "GATE1") (pin "TIP") (pinfunction "TIP_TIP") (pintype "passive"))
      (node (ref "R6") (pin "2") (pinfunction "2_2") (pintype "passive"))
    )
    (net (code "22") (name "Net-(GATE2-PadTIP)") (class "Default")
      (node (ref "GATE2") (pin "TIP") (pinfunction "TIP_TIP") (pintype "passive"))
      (node (ref "R2") (pin "2") (pinfunction "2_2") (pintype "passive"))
    )
    (net (code "23") (name "Net-(GATE3-PadTIP)") (class "Default")
      (node (ref "GATE3") (pin "TIP") (pinfunction "TIP_TIP") (pintype "passive"))
      (node (ref "R8") (pin "2") (pinfunction "2_2") (pintype "passive"))
    )
    (net (code "24") (name "Net-(GATE4-PadTIP)") (class "Default")
      (node (ref "GATE4") (pin "TIP") (pinfunction "TIP_TIP") (pintype "passive"))
      (node (ref "R15") (pin "2") (pinfunction "2_2") (pintype "passive"))
    )
    (net (code "25") (name "Net-(IC1A-O)") (class "Default")
      (node (ref "C27") (pin "1") (pinfunction "1_1") (pintype "passive"))
      (node (ref "IC1") (pin "3") (pinfunction "O_3") (pintype "output"))
    )
    (net (code "26") (name "Net-(IC1B-I0)") (class "Default")
      (node (ref "C28") (pin "2") (pinfunction "2_2") (pintype "passive"))
      (node (ref "IC1") (pin "5") (pinfunction "I0_5") (pintype "input"))
      (node (ref "IC1") (pin "6") (pinfunction "I1_6") (pintype "input"))
      (node (ref "R42") (pin "2") (pinfunction "2_2") (pintype "passive"))
    )
    (net (code "27") (name "Net-(IC1B-O)") (class "Default")
      (node (ref "IC1") (pin "4") (pinfunction "O_4") (pintype "output"))
      (node (ref "R43") (pin "1") (pinfunction "1_1") (pintype "passive"))
    )
    (net (code "28") (name "Net-(IC1C-I0)") (class "Default")
      (node (ref "C26") (pin "2") (pinfunction "2_2") (pintype "passive"))
      (node (ref "IC1") (pin "8") (pinfunction "I0_8") (pintype "input"))
      (node (ref "IC1") (pin "9") (pinfunction "I1_9") (pintype "input"))
      (node (ref "R18") (pin "2") (pinfunction "2_2") (pintype "passive"))
    )
    (net (code "29") (name "Net-(IC1C-O)") (class "Default")
      (node (ref "IC1") (pin "10") (pinfunction "O_10") (pintype "output"))
      (node (ref "R19") (pin "1") (pinfunction "1_1") (pintype "passive"))
    )
    (net (code "30") (name "Net-(IC1D-O)") (class "Default")
      (node (ref "C26") (pin "1") (pinfunction "1_1") (pintype "passive"))
      (node (ref "IC1") (pin "11") (pinfunction "O_11") (pintype "output"))
    )
    (net (code "31") (name "Net-(IC2A-+IN)") (class "Default")
      (node (ref "C18") (pin "1") (pinfunction "1_1") (pintype "passive"))
      (node (ref "IC2") (pin "3") (pinfunction "+IN_3") (pintype "input"))
      (node (ref "IC2") (pin "5") (pinfunction "+IN_5") (pintype "input"))
      (node (ref "R25") (pin "2") (pinfunction "2_2") (pintype "passive"))
    )
    (net (code "32") (name "Net-(IC2A--IN)") (class "Default")
      (node (ref "C19") (pin "1") (pinfunction "1_1") (pintype "passive"))
      (node (ref "IC2") (pin "2") (pinfunction "-IN_2") (pintype "input"))
      (node (ref "R26") (pin "1") (pinfunction "1_1") (pintype "passive"))
      (node (ref "R27") (pin "2") (pinfunction "2_2") (pintype "passive"))
    )
    (net (code "33") (name "Net-(IC2A-OUT)") (class "Default")
      (node (ref "C19") (pin "2") (pinfunction "2_2") (pintype "passive"))
      (node (ref "IC2") (pin "1") (pinfunction "OUT_1") (pintype "output"))
      (node (ref "R29") (pin "1") (pinfunction "1_1") (pintype "passive"))
    )
    (net (code "34") (name "Net-(IC2B--IN)") (class "Default")
      (node (ref "D3") (pin "A") (pinfunction "A_A") (pintype "passive"))
      (node (ref "IC2") (pin "6") (pinfunction "-IN_6") (pintype "input"))
      (node (ref "IC2") (pin "7") (pinfunction "OUT_7") (pintype "output"))
    )
    (net (code "35") (name "Net-(IC2C-+IN)") (class "Default")
      (node (ref "C3") (pin "1") (pinfunction "1_1") (pintype "passive"))
      (node (ref "IC2") (pin "10") (pinfunction "+IN_10") (pintype "input"))
      (node (ref "IC2") (pin "12") (pinfunction "+IN_12") (pintype "input"))
      (node (ref "R20") (pin "2") (pinfunction "2_2") (pintype "passive"))
    )
    (net (code "36") (name "Net-(IC2C--IN)") (class "Default")
      (node (ref "C6") (pin "1") (pinfunction "1_1") (pintype "passive"))
      (node (ref "IC2") (pin "9") (pinfunction "-IN_9") (pintype "input"))
      (node (ref "R21") (pin "1") (pinfunction "1_1") (pintype "passive"))
      (node (ref "R22") (pin "2") (pinfunction "2_2") (pintype "passive"))
    )
    (net (code "37") (name "Net-(IC2C-OUT)") (class "Default")
      (node (ref "C6") (pin "2") (pinfunction "2_2") (pintype "passive"))
      (node (ref "IC2") (pin "8") (pinfunction "OUT_8") (pintype "output"))
      (node (ref "R24") (pin "1") (pinfunction "1_1") (pintype "passive"))
    )
    (net (code "38") (name "Net-(IC2D--IN)") (class "Default")
      (node (ref "D4") (pin "A") (pinfunction "A_A") (pintype "passive"))
      (node (ref "IC2") (pin "13") (pinfunction "-IN_13") (pintype "input"))
      (node (ref "IC2") (pin "14") (pinfunction "OUT_14") (pintype "output"))
    )
    (net (code "39") (name "Net-(IC3A-+IN)") (class "Default")
      (node (ref "C20") (pin "1") (pinfunction "1_1") (pintype "passive"))
      (node (ref "IC3") (pin "3") (pinfunction "+IN_3") (pintype "input"))
      (node (ref "IC3") (pin "5") (pinfunction "+IN_5") (pintype "input"))
      (node (ref "R30") (pin "2") (pinfunction "2_2") (pintype "passive"))
    )
    (net (code "40") (name "Net-(IC3A--IN)") (class "Default")
      (node (ref "C21") (pin "1") (pinfunction "1_1") (pintype "passive"))
      (node (ref "IC3") (pin "2") (pinfunction "-IN_2") (pintype "input"))
      (node (ref "R31") (pin "1") (pinfunction "1_1") (pintype "passive"))
      (node (ref "R32") (pin "2") (pinfunction "2_2") (pintype "passive"))
    )
    (net (code "41") (name "Net-(IC3A-OUT)") (class "Default")
      (node (ref "C21") (pin "2") (pinfunction "2_2") (pintype "passive"))
      (node (ref "IC3") (pin "1") (pinfunction "OUT_1") (pintype "output"))
      (node (ref "R34") (pin "1") (pinfunction "1_1") (pintype "passive"))
    )
    (net (code "42") (name "Net-(IC3B--IN)") (class "Default")
      (node (ref "D5") (pin "A") (pinfunction "A_A") (pintype "passive"))
      (node (ref "IC3") (pin "6") (pinfunction "-IN_6") (pintype "input"))
      (node (ref "IC3") (pin "7") (pinfunction "OUT_7") (pintype "output"))
    )
    (net (code "43") (name "Net-(IC3C-+IN)") (class "Default")
      (node (ref "C22") (pin "1") (pinfunction "1_1") (pintype "passive"))
      (node (ref "IC3") (pin "10") (pinfunction "+IN_10") (pintype "input"))
      (node (ref "IC3") (pin "12") (pinfunction "+IN_12") (pintype "input"))
      (node (ref "R35") (pin "2") (pinfunction "2_2") (pintype "passive"))
    )
    (net (code "44") (name "Net-(IC3C--IN)") (class "Default")
      (node (ref "C23") (pin "1") (pinfunction "1_1") (pintype "passive"))
      (node (ref "IC3") (pin "9") (pinfunction "-IN_9") (pintype "input"))
      (node (ref "R36") (pin "1") (pinfunction "1_1") (pintype "passive"))
      (node (ref "R37") (pin "2") (pinfunction "2_2") (pintype "passive"))
    )
    (net (code "45") (name "Net-(IC3C-OUT)") (class "Default")
      (node (ref "C23") (pin "2") (pinfunction "2_2") (pintype "passive"))
      (node (ref "IC3") (pin "8") (pinfunction "OUT_8") (pintype "output"))
      (node (ref "R39") (pin "1") (pinfunction "1_1") (pintype "passive"))
    )
    (net (code "46") (name "Net-(IC3D--IN)") (class "Default")
      (node (ref "D6") (pin "A") (pinfunction "A_A") (pintype "passive"))
      (node (ref "IC3") (pin "13") (pinfunction "-IN_13") (pintype "input"))
      (node (ref "IC3") (pin "14") (pinfunction "OUT_14") (pintype "output"))
    )
    (net (code "47") (name "Net-(IC4A-I0)") (class "Default")
      (node (ref "C27") (pin "2") (pinfunction "2_2") (pintype "passive"))
      (node (ref "IC4") (pin "1") (pinfunction "I0_1") (pintype "input"))
      (node (ref "IC4") (pin "2") (pinfunction "I1_2") (pintype "input"))
      (node (ref "R40") (pin "2") (pinfunction "2_2") (pintype "passive"))
    )
    (net (code "48") (name "Net-(IC4A-O)") (class "Default")
      (node (ref "IC4") (pin "3") (pinfunction "O_3") (pintype "output"))
      (node (ref "R41") (pin "1") (pinfunction "1_1") (pintype "passive"))
    )
    (net (code "49") (name "Net-(IC4B-O)") (class "Default")
      (node (ref "C28") (pin "1") (pinfunction "1_1") (pintype "passive"))
      (node (ref "IC4") (pin "4") (pinfunction "O_4") (pintype "output"))
    )
    (net (code "50") (name "Net-(IC4C-I0)") (class "Default")
      (node (ref "C25") (pin "2") (pinfunction "2_2") (pintype "passive"))
      (node (ref "IC4") (pin "8") (pinfunction "I0_8") (pintype "input"))
      (node (ref "IC4") (pin "9") (pinfunction "I1_9") (pintype "input"))
      (node (ref "R9") (pin "2") (pinfunction "2_2") (pintype "passive"))
    )
    (net (code "51") (name "Net-(IC4C-O)") (class "Default")
      (node (ref "IC4") (pin "10") (pinfunction "O_10") (pintype "output"))
      (node (ref "R17") (pin "1") (pinfunction "1_1") (pintype "passive"))
    )
    (net (code "52") (name "Net-(IC4D-O)") (class "Default")
      (node (ref "C25") (pin "1") (pinfunction "1_1") (pintype "passive"))
      (node (ref "IC4") (pin "11") (pinfunction "O_11") (pintype "output"))
    )
    (net (code "53") (name "Net-(IC7A-I0)") (class "Default")
      (node (ref "IC7") (pin "1") (pinfunction "I0_1") (pintype "input"))
      (node (ref "R17") (pin "2") (pinfunction "2_2") (pintype "passive"))
    )
    (net (code "54") (name "Net-(IC7A-I1)") (class "Default")
      (node (ref "IC7") (pin "2") (pinfunction "I1_2") (pintype "input"))
      (node (ref "R19") (pin "2") (pinfunction "2_2") (pintype "passive"))
    )
    (net (code "55") (name "Net-(IC7B-I0)") (class "Default")
      (node (ref "IC7") (pin "4") (pinfunction "I0_4") (pintype "input"))
      (node (ref "R41") (pin "2") (pinfunction "2_2") (pintype "passive"))
    )
    (net (code "56") (name "Net-(IC7B-I1)") (class "Default")
      (node (ref "IC7") (pin "5") (pinfunction "I1_5") (pintype "input"))
      (node (ref "R43") (pin "2") (pinfunction "2_2") (pintype "passive"))
    )
    (net (code "57") (name "Net-(OUTPUT1-PadTIP)") (class "Default")
      (node (ref "OUTPUT1") (pin "TIP") (pinfunction "TIP_TIP") (pintype "passive"))
      (node (ref "R26") (pin "2") (pinfunction "2_2") (pintype "passive"))
      (node (ref "R29") (pin "2") (pinfunction "2_2") (pintype "passive"))
    )
    (net (code "58") (name "Net-(OUTPUT2-PadTIP)") (class "Default")
      (node (ref "OUTPUT2") (pin "TIP") (pinfunction "TIP_TIP") (pintype "passive"))
      (node (ref "R21") (pin "2") (pinfunction "2_2") (pintype "passive"))
      (node (ref "R24") (pin "2") (pinfunction "2_2") (pintype "passive"))
    )
    (net (code "59") (name "Net-(OUTPUT3-PadTIP)") (class "Default")
      (node (ref "OUTPUT3") (pin "TIP") (pinfunction "TIP_TIP") (pintype "passive"))
      (node (ref "R31") (pin "2") (pinfunction "2_2") (pintype "passive"))
      (node (ref "R34") (pin "2") (pinfunction "2_2") (pintype "passive"))
    )
    (net (code "60") (name "Net-(OUTPUT4-PadTIP)") (class "Default")
      (node (ref "OUTPUT4") (pin "TIP") (pinfunction "TIP_TIP") (pintype "passive"))
      (node (ref "R36") (pin "2") (pinfunction "2_2") (pintype "passive"))
      (node (ref "R39") (pin "2") (pinfunction "2_2") (pintype "passive"))
    )
    (net (code "61") (name "Net-(U1-PB6(XTAL1{slash}TOSC1))") (class "Default")
      (node (ref "C1") (pin "1") (pinfunction "1_1") (pintype "passive"))
      (node (ref "Q1") (pin "2") (pinfunction "2_2") (pintype "passive"))
      (node (ref "U1") (pin "7") (pinfunction "PB6(XTAL1/TOSC1)_7") (pintype "bidirectional"))
    )
    (net (code "62") (name "Net-(U1-PB7(XTAL2{slash}TOSC2))") (class "Default")
      (node (ref "C2") (pin "1") (pinfunction "1_1") (pintype "passive"))
      (node (ref "Q1") (pin "1") (pinfunction "1_1") (pintype "passive"))
      (node (ref "U1") (pin "8") (pinfunction "PB7(XTAL2/TOSC2)_8") (pintype "bidirectional"))
    )
    (net (code "63") (name "Net-(U4-Z)") (class "Default")
      (node (ref "R60") (pin "2") (pinfunction "2_2") (pintype "passive"))
      (node (ref "U4") (pin "3") (pinfunction "Z_3") (pintype "bidirectional"))
    )
    (net (code "64") (name "POT_A") (class "Default")
      (node (ref "POT_A") (pin "P$2") (pinfunction "2_P$2") (pintype "passive"))
      (node (ref "U4") (pin "13") (pinfunction "Y0_13") (pintype "bidirectional"))
    )
    (net (code "65") (name "POT_D") (class "Default")
      (node (ref "POT_D") (pin "P$2") (pinfunction "2_P$2") (pintype "passive"))
      (node (ref "U4") (pin "14") (pinfunction "Y1_14") (pintype "bidirectional"))
    )
    (net (code "66") (name "POT_R") (class "Default")
      (node (ref "POT_R") (pin "P$2") (pinfunction "2_P$2") (pintype "passive"))
      (node (ref "U4") (pin "12") (pinfunction "Y3_12") (pintype "bidirectional"))
    )
    (net (code "67") (name "POT_S") (class "Default")
      (node (ref "POT_S") (pin "P$2") (pinfunction "2_P$2") (pintype "passive"))
      (node (ref "U4") (pin "15") (pinfunction "Y2_15") (pintype "bidirectional"))
    )
    (net (code "68") (name "POT_SA") (class "Default")
      (node (ref "POT_SA") (pin "P$2") (pinfunction "2_P$2") (pintype "passive"))
      (node (ref "U4") (pin "1") (pinfunction "Y4_1") (pintype "bidirectional"))
    )
    (net (code "69") (name "POT_SD") (class "Default")
      (node (ref "POT_SD") (pin "P$2") (pinfunction "2_P$2") (pintype "passive"))
      (node (ref "U4") (pin "5") (pinfunction "Y5_5") (pintype "bidirectional"))
    )
    (net (code "70") (name "POT_SR") (class "Default")
      (node (ref "POT_SR") (pin "P$2") (pinfunction "2_P$2") (pintype "passive"))
      (node (ref "U4") (pin "4") (pinfunction "Y7_4") (pintype "bidirectional"))
    )
    (net (code "71") (name "POT_ST") (class "Default")
      (node (ref "POT_ST") (pin "P$2") (pinfunction "2_P$2") (pintype "passive"))
      (node (ref "U4") (pin "2") (pinfunction "Y6_2") (pintype "bidirectional"))
    )
    (net (code "72") (name "RST") (class "Default")
      (node (ref "ISP1") (pin "5") (pinfunction "RST_5") (pintype "output"))
      (node (ref "U1") (pin "29") (pinfunction "PC6(/RESET)_29") (pintype "bidirectional"))
    )
    (net (code "73") (name "S0") (class "Default")
      (node (ref "U1") (pin "23") (pinfunction "PC0(ADC0)_23") (pintype "bidirectional"))
      (node (ref "U4") (pin "11") (pinfunction "S0_11") (pintype "input"))
    )
    (net (code "74") (name "S1") (class "Default")
      (node (ref "U1") (pin "24") (pinfunction "PC1(ADC1)_24") (pintype "bidirectional"))
      (node (ref "U4") (pin "10") (pinfunction "S1_10") (pintype "input"))
    )
    (net (code "75") (name "S2") (class "Default")
      (node (ref "U1") (pin "25") (pinfunction "PC2(ADC2)_25") (pintype "bidirectional"))
      (node (ref "U4") (pin "9") (pinfunction "S2_9") (pintype "input"))
    )
    (net (code "76") (name "SCK") (class "Default")
      (node (ref "ISP1") (pin "3") (pinfunction "SCK_3") (pintype "output"))
      (node (ref "U$3") (pin "4") (pinfunction "SCK_4") (pintype "input"))
      (node (ref "U$4") (pin "4") (pinfunction "SCK_4") (pintype "input"))
      (node (ref "U1") (pin "17") (pinfunction "PB5(SCK)_17") (pintype "bidirectional"))
    )
    (net (code "77") (name "TRIG") (class "Default")
      (node (ref "IC7") (pin "3") (pinfunction "O_3") (pintype "output"))
      (node (ref "U1") (pin "32") (pinfunction "PD2(INT0)_32") (pintype "bidirectional"))
    )
    (net (code "78") (name "TRIG1") (class "Default")
      (node (ref "IC4") (pin "12") (pinfunction "I0_12") (pintype "input"))
      (node (ref "IC4") (pin "13") (pinfunction "I1_13") (pintype "input"))
      (node (ref "R5") (pin "1") (pinfunction "1_1") (pintype "passive"))
      (node (ref "U1") (pin "27") (pinfunction "PC4(ADC4/SDA)_27") (pintype "bidirectional"))
      (node (ref "U2") (pin "1") (pinfunction "C1_2_1") (pintype "passive"))
    )
    (net (code "79") (name "TRIG2") (class "Default")
      (node (ref "IC1") (pin "12") (pinfunction "I0_12") (pintype "input"))
      (node (ref "IC1") (pin "13") (pinfunction "I1_13") (pintype "input"))
      (node (ref "IC7") (pin "6") (pinfunction "O_6") (pintype "output"))
      (node (ref "R1") (pin "1") (pinfunction "1_1") (pintype "passive"))
      (node (ref "U1") (pin "1") (pinfunction "PD3(INT1)_1") (pintype "bidirectional"))
      (node (ref "U1") (pin "28") (pinfunction "PC5(ADC5/SCL)_28") (pintype "bidirectional"))
      (node (ref "U2") (pin "3") (pinfunction "C2_2_3") (pintype "passive"))
    )
    (net (code "80") (name "TRIG3") (class "Default")
      (node (ref "IC1") (pin "1") (pinfunction "I0_1") (pintype "input"))
      (node (ref "IC1") (pin "2") (pinfunction "I1_2") (pintype "input"))
      (node (ref "R4") (pin "1") (pinfunction "1_1") (pintype "passive"))
      (node (ref "U1") (pin "19") (pinfunction "ADC6_19") (pintype "bidirectional"))
      (node (ref "U2") (pin "5") (pinfunction "C3_2_5") (pintype "passive"))
    )
    (net (code "81") (name "TRIG4") (class "Default")
      (node (ref "IC4") (pin "5") (pinfunction "I0_5") (pintype "input"))
      (node (ref "IC4") (pin "6") (pinfunction "I1_6") (pintype "input"))
      (node (ref "R14") (pin "1") (pinfunction "1_1") (pintype "passive"))
      (node (ref "U1") (pin "22") (pinfunction "ADC7_22") (pintype "bidirectional"))
      (node (ref "U2") (pin "7") (pinfunction "C4_2_7") (pintype "passive"))
    )
    (net (code "82") (name "VOUTA") (class "Default")
      (node (ref "R25") (pin "1") (pinfunction "1_1") (pintype "passive"))
      (node (ref "U$3") (pin "14") (pinfunction "VOUTA_14") (pintype "output"))
    )
    (net (code "83") (name "VOUTB") (class "Default")
      (node (ref "R20") (pin "1") (pinfunction "1_1") (pintype "passive"))
      (node (ref "U$3") (pin "10") (pinfunction "VOUTB_10") (pintype "output"))
    )
    (net (code "84") (name "VOUTC") (class "Default")
      (node (ref "R30") (pin "1") (pinfunction "1_1") (pintype "passive"))
      (node (ref "U$4") (pin "14") (pinfunction "VOUTA_14") (pintype "output"))
    )
    (net (code "85") (name "VOUTD") (class "Default")
      (node (ref "R35") (pin "1") (pinfunction "1_1") (pintype "passive"))
      (node (ref "U$4") (pin "10") (pinfunction "VOUTB_10") (pintype "output"))
    )
    (net (code "86") (name "unconnected-(GATE1-PadNORM)") (class "Default")
      (node (ref "GATE1") (pin "NORM") (pinfunction "NORM_NORM") (pintype "passive"))
    )
    (net (code "87") (name "unconnected-(GATE2-PadNORM)") (class "Default")
      (node (ref "GATE2") (pin "NORM") (pinfunction "NORM_NORM") (pintype "passive"))
    )
    (net (code "88") (name "unconnected-(GATE3-PadNORM)") (class "Default")
      (node (ref "GATE3") (pin "NORM") (pinfunction "NORM_NORM") (pintype "passive"))
    )
    (net (code "89") (name "unconnected-(GATE4-PadNORM)") (class "Default")
      (node (ref "GATE4") (pin "NORM") (pinfunction "NORM_NORM") (pintype "passive"))
    )
    (net (code "90") (name "unconnected-(OUTPUT1-PadNORM)") (class "Default")
      (node (ref "OUTPUT1") (pin "NORM") (pinfunction "NORM_NORM") (pintype "passive"))
    )
    (net (code "91") (name "unconnected-(OUTPUT2-PadNORM)") (class "Default")
      (node (ref "OUTPUT2") (pin "NORM") (pinfunction "NORM_NORM") (pintype "passive"))
    )
    (net (code "92") (name "unconnected-(OUTPUT3-PadNORM)") (class "Default")
      (node (ref "OUTPUT3") (pin "NORM") (pinfunction "NORM_NORM") (pintype "passive"))
    )
    (net (code "93") (name "unconnected-(OUTPUT4-PadNORM)") (class "Default")
      (node (ref "OUTPUT4") (pin "NORM") (pinfunction "NORM_NORM") (pintype "passive"))
    )
    (net (code "94") (name "unconnected-(U1-AREF-Pad20)") (class "Default")
      (node (ref "U1") (pin "20") (pinfunction "AREF_20") (pintype "bidirectional"))
    )
    (net (code "95") (name "unconnected-(U1-PB0(ICP)-Pad12)") (class "Default")
      (node (ref "U1") (pin "12") (pinfunction "PB0(ICP)_12") (pintype "bidirectional"))
    )
    (net (code "96") (name "unconnected-(U1-PD0(RXD)-Pad30)") (class "Default")
      (node (ref "U1") (pin "30") (pinfunction "PD0(RXD)_30") (pintype "bidirectional"))
    )
    (net (code "97") (name "unconnected-(U1-PD1(TXD)-Pad31)") (class "Default")
      (node (ref "U1") (pin "31") (pinfunction "PD1(TXD)_31") (pintype "bidirectional"))
    )
    (net (code "98") (name "unconnected-(U1-PD4(XCK{slash}T0)-Pad2)") (class "Default")
      (node (ref "U1") (pin "2") (pinfunction "PD4(XCK/T0)_2") (pintype "bidirectional"))
    )
    (net (code "99") (name "unconnected-(U1-PD5(T1)-Pad9)") (class "Default")
      (node (ref "U1") (pin "9") (pinfunction "PD5(T1)_9") (pintype "bidirectional"))
    )
    (net (code "100") (name "unconnected-(U1-PD6(AIN0)-Pad10)") (class "Default")
      (node (ref "U1") (pin "10") (pinfunction "PD6(AIN0)_10") (pintype "bidirectional"))
    )
    (net (code "101") (name "unconnected-(U1-PD7(AIN1)-Pad11)") (class "Default")
      (node (ref "U1") (pin "11") (pinfunction "PD7(AIN1)_11") (pintype "bidirectional"))
    )
    (net (code "102") (name "unconnected-(U2-C1-Pad2)") (class "Default")
      (node (ref "U2") (pin "2") (pinfunction "C1_2") (pintype "passive"))
    )
    (net (code "103") (name "unconnected-(U2-C2-Pad4)") (class "Default")
      (node (ref "U2") (pin "4") (pinfunction "C2_4") (pintype "passive"))
    )
    (net (code "104") (name "unconnected-(U2-C3-Pad6)") (class "Default")
      (node (ref "U2") (pin "6") (pinfunction "C3_6") (pintype "passive"))
    )
    (net (code "105") (name "unconnected-(U2-C4-Pad8)") (class "Default")
      (node (ref "U2") (pin "8") (pinfunction "C4_8") (pintype "passive"))
    )
  )
)
